# MCU.net
KiCad netlist of a schematic drawn in Altium Designer
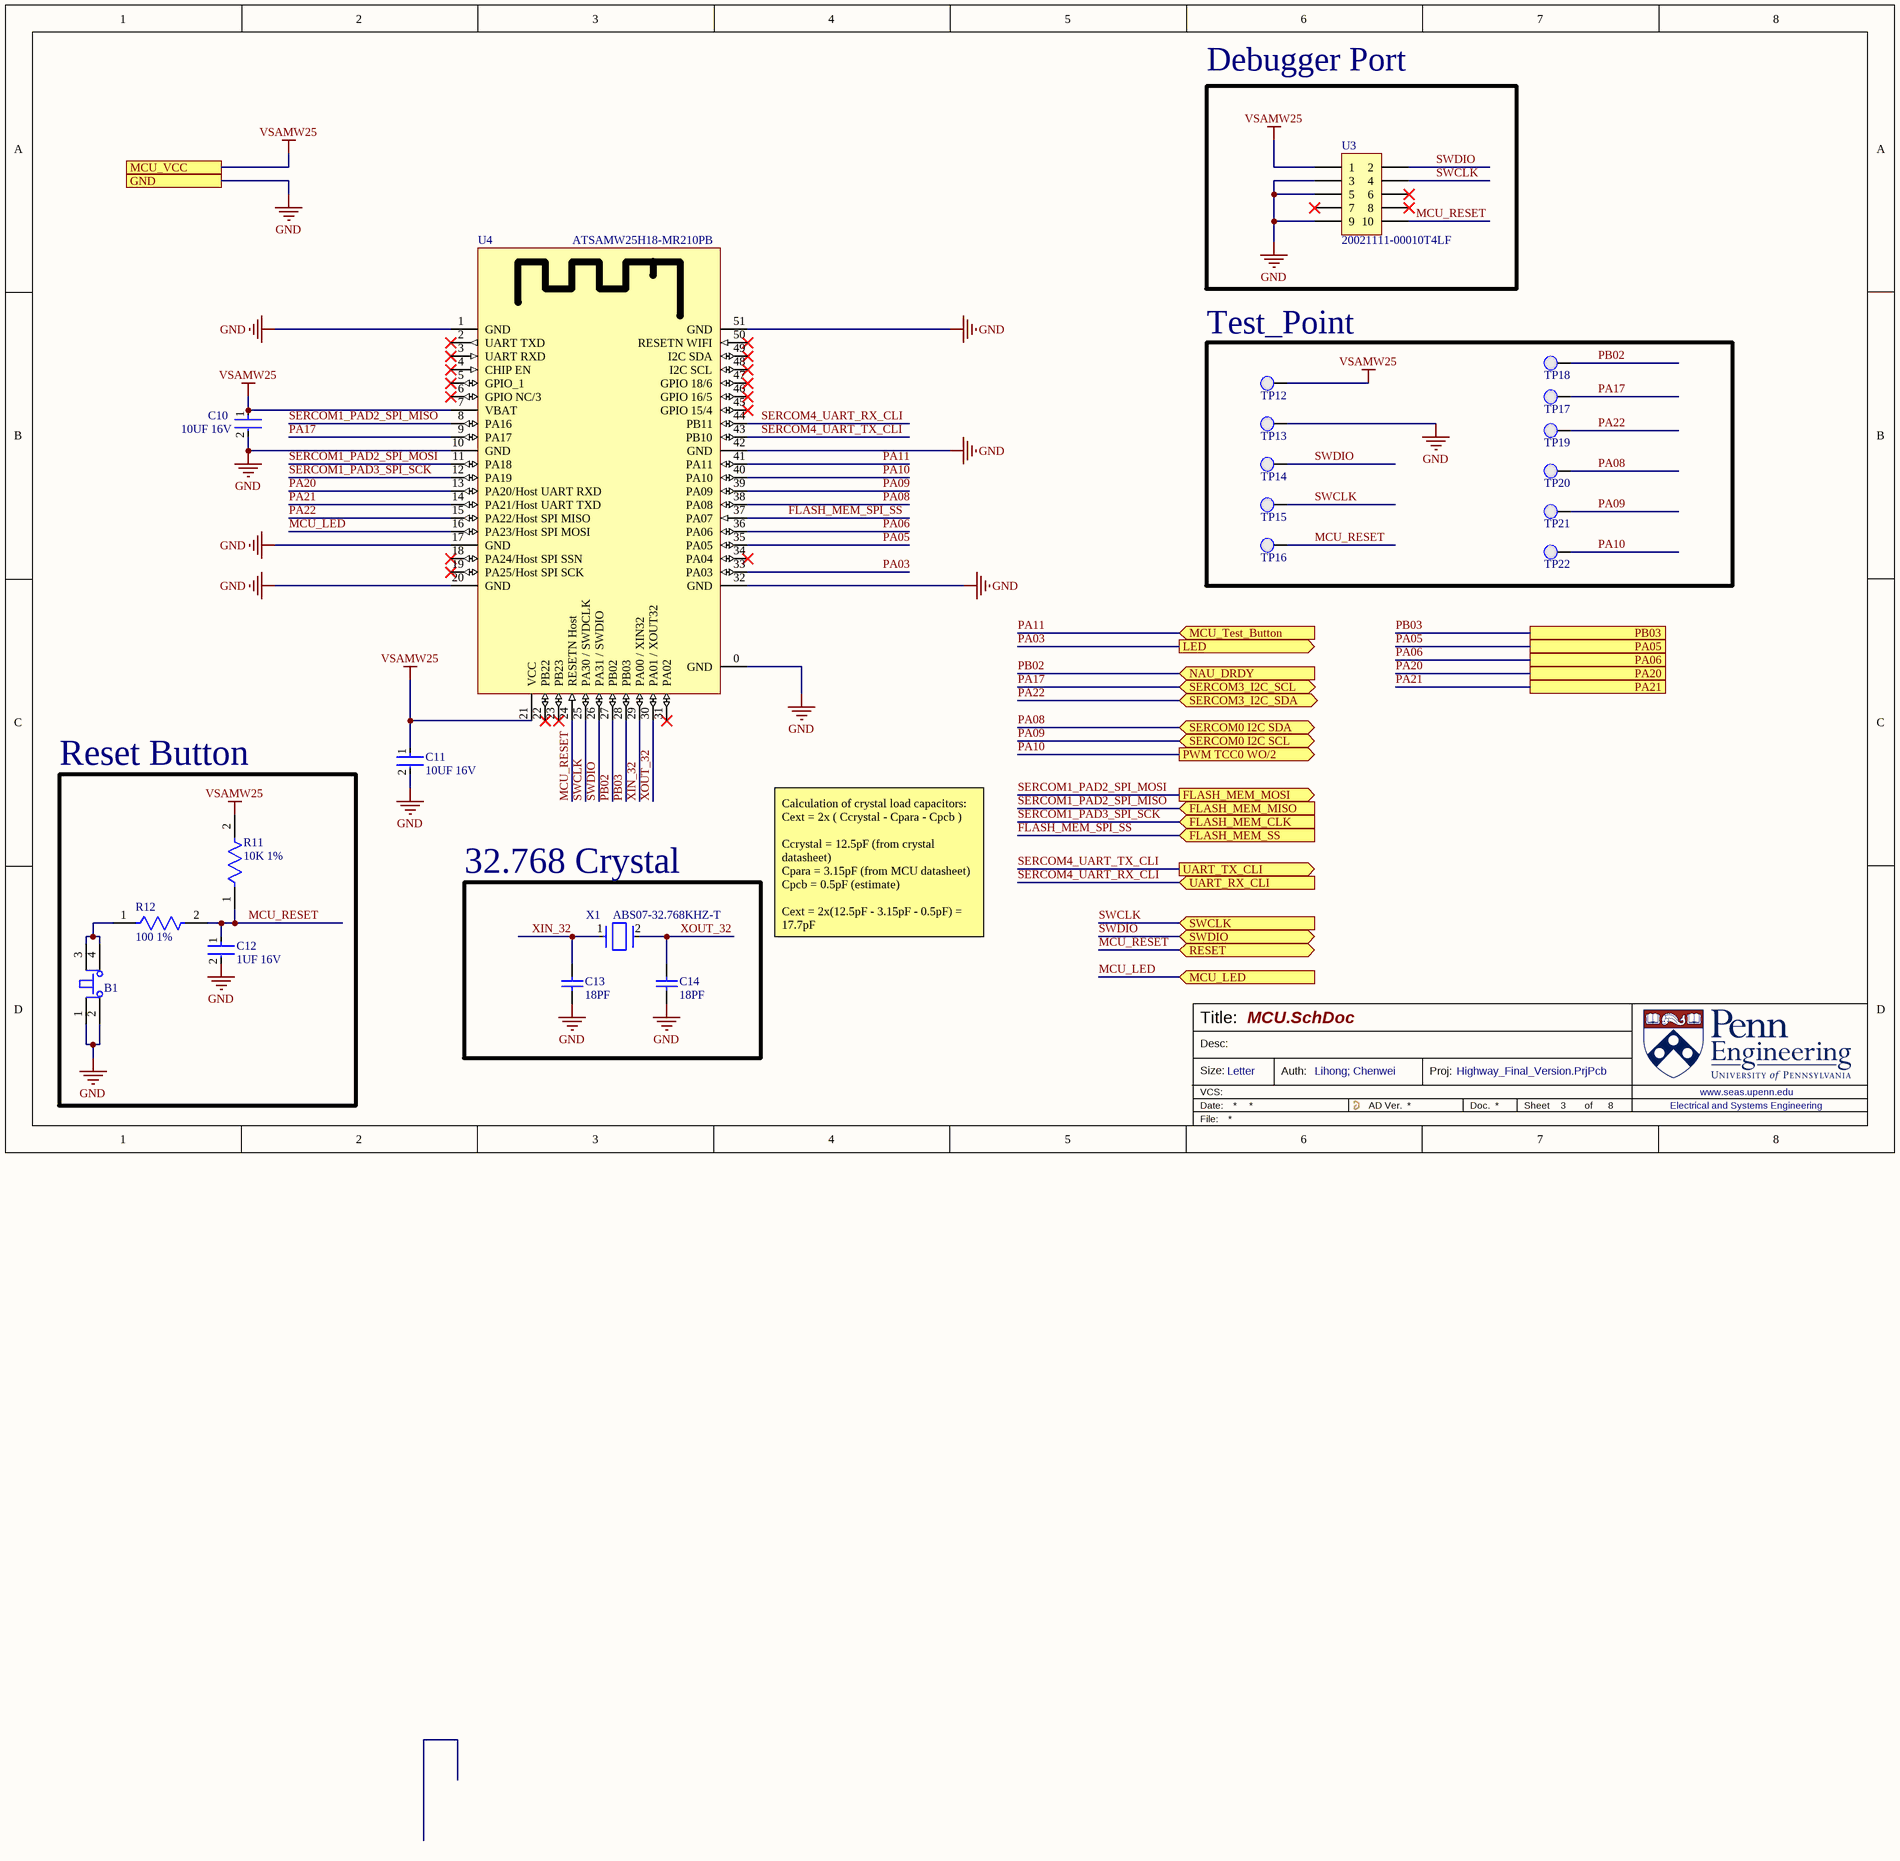
[diagram p0: MCU.SchDoc]

(export (version "E")
  (design (tool "Eeschema 10.0.6"))
  (components
    (comp (ref "B1")
      (value "PTS810SJK250SMTRLFS")
      (footprint "PTS810SJK250SMTRLFS-Footprint-1")
      (libsource (lib "University of Pennsylvania (ESE Labs)") (part "Tactile Switch 4 Pin"))
    )
    (comp (ref "C10")
      (value "10UF 16V")
      (footprint "FP-CC0603-DB-MFG")
      (description "CAP CER 10UF 6.3V X5R 0603")
      (fields (field (name "TOLERANCE") "20%"))
      (libsource (lib "Altium Content Vault") (part "e9c51b7dd13d4faca003ae77663ab08"))
    )
    (comp (ref "C11")
      (value "10UF 16V")
      (footprint "FP-CC0603-DB-MFG")
      (description "CAP CER 10UF 6.3V X5R 0603")
      (fields (field (name "TOLERANCE") "20%"))
      (libsource (lib "Altium Content Vault") (part "e9c51b7dd13d4faca003ae77663ab08"))
    )
    (comp (ref "C12")
      (value "1UF 16V")
      (footprint "FP-CC0603-DA-MFG")
      (description "CC0603 1 uF X7R 10.00% 16 V")
      (fields (field (name "MANUFACTURER") "YAGEO") (field (name "TOLERANCE") "0.1"))
      (libsource (lib "Altium Content Vault") (part "11868f565c42a9108669ba33697ecf6"))
    )
    (comp (ref "C13")
      (value "18PF")
      (footprint "CAPC1608X90X40LL10T20")
      (description "Chip Capacitor, 18 pF, +/- 5%, 50 V, -55 to 125 degC, 0603 (1608 Metric), RoHS, Tape and Reel")
      (fields (field (name "TOLERANCE") "1%"))
      (libsource (lib "Altium Content Vault") (part "CAP-NP-2"))
    )
    (comp (ref "C14")
      (value "18PF")
      (footprint "CAPC1608X90X40LL10T20")
      (description "Chip Capacitor, 18 pF, +/- 5%, 50 V, -55 to 125 degC, 0603 (1608 Metric), RoHS, Tape and Reel")
      (fields (field (name "TOLERANCE") "1%"))
      (libsource (lib "Altium Content Vault") (part "CAP-NP-2"))
    )
    (comp (ref "R11")
      (value "10K 1%")
      (footprint "FP-RNCP0603-IPC_A")
      (description "10kΩ ±1% 0.125W 0603 High Power Anti-Sulfur Thin Film Chip Resistor")
      (fields (field (name "TOLERANCE") "1%"))
      (libsource (lib "Altium Content Vault") (part "1029c3af85768c4190bb7ad29bc67b5"))
    )
    (comp (ref "R12")
      (value "100 1%")
      (footprint "FP-RMCF0603-IPC_C")
      (description "100Ω ±1% 0.1W 0603 Thick Film Chip Resistor AEC-Q200 compliant")
      (fields (field (name "TOLERANCE") "1%"))
      (libsource (lib "Altium Content Vault") (part "1029c3af85768c4190bb7ad29bc67b5"))
    )
    (comp (ref "TP12")
      (value "Test Point 0.1\"")
      (footprint "Test Point 0.1\"-Footprint-1")
      (libsource (lib "University of Pennsylvania (ESE Labs)") (part "Test Point 0.1{dblquote}-Symbol-1"))
    )
    (comp (ref "TP13")
      (value "Test Point 0.1\"")
      (footprint "Test Point 0.1\"-Footprint-1")
      (libsource (lib "University of Pennsylvania (ESE Labs)") (part "Test Point 0.1{dblquote}-Symbol-1"))
    )
    (comp (ref "TP14")
      (value "Test Point 0.1\"")
      (footprint "Test Point 0.1\"-Footprint-1")
      (libsource (lib "University of Pennsylvania (ESE Labs)") (part "Test Point 0.1{dblquote}-Symbol-1"))
    )
    (comp (ref "TP15")
      (value "Test Point 0.1\"")
      (footprint "Test Point 0.1\"-Footprint-1")
      (libsource (lib "University of Pennsylvania (ESE Labs)") (part "Test Point 0.1{dblquote}-Symbol-1"))
    )
    (comp (ref "TP16")
      (value "Test Point 0.1\"")
      (footprint "Test Point 0.1\"-Footprint-1")
      (libsource (lib "University of Pennsylvania (ESE Labs)") (part "Test Point 0.1{dblquote}-Symbol-1"))
    )
    (comp (ref "TP17")
      (value "Test Point 0.1\"")
      (footprint "Test Point 0.1\"-Footprint-1")
      (libsource (lib "University of Pennsylvania (ESE Labs)") (part "Test Point 0.1{dblquote}-Symbol-1"))
    )
    (comp (ref "TP18")
      (value "Test Point 0.1\"")
      (footprint "Test Point 0.1\"-Footprint-1")
      (libsource (lib "University of Pennsylvania (ESE Labs)") (part "Test Point 0.1{dblquote}-Symbol-1"))
    )
    (comp (ref "TP19")
      (value "Test Point 0.1\"")
      (footprint "Test Point 0.1\"-Footprint-1")
      (libsource (lib "University of Pennsylvania (ESE Labs)") (part "Test Point 0.1{dblquote}-Symbol-1"))
    )
    (comp (ref "TP20")
      (value "Test Point 0.1\"")
      (footprint "Test Point 0.1\"-Footprint-1")
      (libsource (lib "University of Pennsylvania (ESE Labs)") (part "Test Point 0.1{dblquote}-Symbol-1"))
    )
    (comp (ref "TP21")
      (value "Test Point 0.1\"")
      (footprint "Test Point 0.1\"-Footprint-1")
      (libsource (lib "University of Pennsylvania (ESE Labs)") (part "Test Point 0.1{dblquote}-Symbol-1"))
    )
    (comp (ref "TP22")
      (value "Test Point 0.1\"")
      (footprint "Test Point 0.1\"-Footprint-1")
      (libsource (lib "University of Pennsylvania (ESE Labs)") (part "Test Point 0.1{dblquote}-Symbol-1"))
    )
    (comp (ref "U3")
      (value "20021111-00010T4LF")
      (footprint "20021111-00010T4LF-Footprint-1")
      (libsource (lib "University of Pennsylvania (ESE Labs)") (part "20021111-00010T4LF-Symbol-1"))
    )
    (comp (ref "U4")
      (value "ATSAMW25H18-MR210PB")
      (footprint "SAMW25H18-MR510PB-Footprint-1")
      (description "2.7 - 4.2 V 65 Mbps 17 dbm 256 kB Flash 32 kB SRAM 802.11 b/g/n Smart Module")
      (libsource (lib "University of Pennsylvania (ESE Labs)") (part "SAMW25H18-MR510PB-Symbol-1"))
    )
    (comp (ref "X1")
      (value "ABS07-32.768KHZ-T")
      (footprint "FP-ABS07-MFG")
      (description "Crystal 32.768kHz ±20ppm (Tol) 12.5pF FUND 70kΩ 2-Pin CSMD T/R")
      (fields (field (name "TOLERANCE") "20ppm"))
      (libsource (lib "Altium Content Vault") (part "c23a69dc6c9e2f18f2079038eb95dd1"))
    )
  )
  (nets
    (net (code "1") (name "/FLASH_MEM_SPI_SS") (class "Default")
      (node (ref "U4") (pin "37") (pinfunction "PA07_37") (pintype "input"))
    )
    (net (code "2") (name "/MCU_LED") (class "Default")
      (node (ref "U4") (pin "16") (pinfunction "PA23/Host_SPI_MOSI_16") (pintype "bidirectional"))
    )
    (net (code "3") (name "/MCU_RESET") (class "Default")
      (node (ref "C12") (pin "1") (pinfunction "1_1") (pintype "passive"))
      (node (ref "R11") (pin "1") (pinfunction "1_1") (pintype "passive"))
      (node (ref "R12") (pin "2") (pinfunction "2_2") (pintype "passive"))
      (node (ref "TP16") (pin "1") (pinfunction "PAD_1") (pintype "passive"))
      (node (ref "U3") (pin "10") (pinfunction "10_10") (pintype "passive"))
      (node (ref "U4") (pin "24") (pinfunction "RESETN_Host_24") (pintype "input"))
    )
    (net (code "4") (name "/PA03") (class "Default")
      (node (ref "U4") (pin "33") (pinfunction "PA03_33") (pintype "bidirectional"))
    )
    (net (code "5") (name "/PA05") (class "Default")
      (node (ref "U4") (pin "35") (pinfunction "PA05_35") (pintype "bidirectional"))
    )
    (net (code "6") (name "/PA06") (class "Default")
      (node (ref "U4") (pin "36") (pinfunction "PA06_36") (pintype "bidirectional"))
    )
    (net (code "7") (name "/PA08") (class "Default")
      (node (ref "TP20") (pin "1") (pinfunction "PAD_1") (pintype "passive"))
      (node (ref "U4") (pin "38") (pinfunction "PA08_38") (pintype "bidirectional"))
    )
    (net (code "8") (name "/PA09") (class "Default")
      (node (ref "TP21") (pin "1") (pinfunction "PAD_1") (pintype "passive"))
      (node (ref "U4") (pin "39") (pinfunction "PA09_39") (pintype "bidirectional"))
    )
    (net (code "9") (name "/PA10") (class "Default")
      (node (ref "TP22") (pin "1") (pinfunction "PAD_1") (pintype "passive"))
      (node (ref "U4") (pin "40") (pinfunction "PA10_40") (pintype "bidirectional"))
    )
    (net (code "10") (name "/PA11") (class "Default")
      (node (ref "U4") (pin "41") (pinfunction "PA11_41") (pintype "bidirectional"))
    )
    (net (code "11") (name "/PA17") (class "Default")
      (node (ref "TP17") (pin "1") (pinfunction "PAD_1") (pintype "passive"))
      (node (ref "U4") (pin "9") (pinfunction "PA17_9") (pintype "bidirectional"))
    )
    (net (code "12") (name "/PA20") (class "Default")
      (node (ref "U4") (pin "13") (pinfunction "PA20/Host_UART_RXD_13") (pintype "bidirectional"))
    )
    (net (code "13") (name "/PA21") (class "Default")
      (node (ref "U4") (pin "14") (pinfunction "PA21/Host_UART_TXD_14") (pintype "bidirectional"))
    )
    (net (code "14") (name "/PA22") (class "Default")
      (node (ref "TP19") (pin "1") (pinfunction "PAD_1") (pintype "passive"))
      (node (ref "U4") (pin "15") (pinfunction "PA22/Host_SPI_MISO_15") (pintype "bidirectional"))
    )
    (net (code "15") (name "/PB02") (class "Default")
      (node (ref "TP18") (pin "1") (pinfunction "PAD_1") (pintype "passive"))
      (node (ref "U4") (pin "27") (pinfunction "PB02_27") (pintype "bidirectional"))
    )
    (net (code "16") (name "/PB03") (class "Default")
      (node (ref "U4") (pin "28") (pinfunction "PB03_28") (pintype "bidirectional"))
    )
    (net (code "17") (name "/SERCOM1_PAD2_SPI_MISO") (class "Default")
      (node (ref "U4") (pin "8") (pinfunction "PA16_8") (pintype "bidirectional"))
    )
    (net (code "18") (name "/SERCOM1_PAD2_SPI_MOSI") (class "Default")
      (node (ref "U4") (pin "11") (pinfunction "PA18_11") (pintype "bidirectional"))
    )
    (net (code "19") (name "/SERCOM1_PAD3_SPI_SCK") (class "Default")
      (node (ref "U4") (pin "12") (pinfunction "PA19_12") (pintype "bidirectional"))
    )
    (net (code "20") (name "/SERCOM4_UART_RX_CLI") (class "Default")
      (node (ref "U4") (pin "44") (pinfunction "PB11_44") (pintype "bidirectional"))
    )
    (net (code "21") (name "/SERCOM4_UART_TX_CLI") (class "Default")
      (node (ref "U4") (pin "43") (pinfunction "PB10_43") (pintype "bidirectional"))
    )
    (net (code "22") (name "/SWCLK") (class "Default")
      (node (ref "TP15") (pin "1") (pinfunction "PAD_1") (pintype "passive"))
      (node (ref "U3") (pin "4") (pinfunction "4_4") (pintype "passive"))
      (node (ref "U4") (pin "25") (pinfunction "PA30_/_SWDCLK_25") (pintype "bidirectional"))
    )
    (net (code "23") (name "/SWDIO") (class "Default")
      (node (ref "TP14") (pin "1") (pinfunction "PAD_1") (pintype "passive"))
      (node (ref "U3") (pin "2") (pinfunction "2_2") (pintype "passive"))
      (node (ref "U4") (pin "26") (pinfunction "PA31_/_SWDIO_26") (pintype "bidirectional"))
    )
    (net (code "24") (name "/XIN_32") (class "Default")
      (node (ref "C13") (pin "2") (pinfunction "2_2") (pintype "passive"))
      (node (ref "U4") (pin "29") (pinfunction "PA00_/_XIN32_29") (pintype "bidirectional"))
      (node (ref "X1") (pin "1") (pinfunction "1_1") (pintype "passive"))
    )
    (net (code "25") (name "/XOUT_32") (class "Default")
      (node (ref "C14") (pin "1") (pinfunction "1_1") (pintype "passive"))
      (node (ref "U4") (pin "30") (pinfunction "PA01_/_XOUT32_30") (pintype "bidirectional"))
      (node (ref "X1") (pin "2") (pinfunction "2_2") (pintype "passive"))
    )
    (net (code "26") (name "GND") (class "Default")
      (node (ref "B1") (pin "1") (pinfunction "1_1") (pintype "passive"))
      (node (ref "B1") (pin "2") (pinfunction "2_2") (pintype "passive"))
      (node (ref "C10") (pin "2") (pinfunction "2_2") (pintype "passive"))
      (node (ref "C11") (pin "2") (pinfunction "2_2") (pintype "passive"))
      (node (ref "C12") (pin "2") (pinfunction "2_2") (pintype "passive"))
      (node (ref "C13") (pin "1") (pinfunction "1_1") (pintype "passive"))
      (node (ref "C14") (pin "2") (pinfunction "2_2") (pintype "passive"))
      (node (ref "TP13") (pin "1") (pinfunction "PAD_1") (pintype "passive"))
      (node (ref "U3") (pin "3") (pinfunction "3_3") (pintype "passive"))
      (node (ref "U3") (pin "5") (pinfunction "5_5") (pintype "passive"))
      (node (ref "U3") (pin "9") (pinfunction "9_9") (pintype "passive"))
      (node (ref "U4") (pin "0") (pinfunction "GND_0") (pintype "power_in"))
      (node (ref "U4") (pin "1") (pinfunction "GND_1") (pintype "power_in"))
      (node (ref "U4") (pin "10") (pinfunction "GND_10") (pintype "power_in"))
      (node (ref "U4") (pin "17") (pinfunction "GND_17") (pintype "power_in"))
      (node (ref "U4") (pin "20") (pinfunction "GND_20") (pintype "power_in"))
      (node (ref "U4") (pin "32") (pinfunction "GND_32") (pintype "power_in"))
      (node (ref "U4") (pin "42") (pinfunction "GND_42") (pintype "power_in"))
      (node (ref "U4") (pin "51") (pinfunction "GND_51") (pintype "power_in"))
    )
    (net (code "27") (name "Net-(B1-2-Pad3)") (class "Default")
      (node (ref "B1") (pin "3") (pinfunction "2_3") (pintype "passive"))
      (node (ref "B1") (pin "4") (pinfunction "4_4") (pintype "passive"))
      (node (ref "R12") (pin "1") (pinfunction "1_1") (pintype "passive"))
    )
    (net (code "28") (name "VSAMW25") (class "Default")
      (node (ref "C10") (pin "1") (pinfunction "1_1") (pintype "passive"))
      (node (ref "C11") (pin "1") (pinfunction "1_1") (pintype "passive"))
      (node (ref "R11") (pin "2") (pinfunction "2_2") (pintype "passive"))
      (node (ref "TP12") (pin "1") (pinfunction "PAD_1") (pintype "passive"))
      (node (ref "U3") (pin "1") (pinfunction "1_1") (pintype "passive"))
      (node (ref "U4") (pin "21") (pinfunction "VCC_21") (pintype "power_in"))
      (node (ref "U4") (pin "7") (pinfunction "VBAT_7") (pintype "power_in"))
    )
    (net (code "29") (name "unconnected-(U3-Pad6)") (class "Default")
      (node (ref "U3") (pin "6") (pinfunction "6_6") (pintype "passive+no_connect"))
    )
    (net (code "30") (name "unconnected-(U3-Pad7)") (class "Default")
      (node (ref "U3") (pin "7") (pinfunction "7_7") (pintype "passive+no_connect"))
    )
    (net (code "31") (name "unconnected-(U3-Pad8)") (class "Default")
      (node (ref "U3") (pin "8") (pinfunction "8_8") (pintype "passive+no_connect"))
    )
    (net (code "32") (name "unconnected-(U4-CHIP_EN-Pad4)") (class "Default")
      (node (ref "U4") (pin "4") (pinfunction "CHIP_EN_4") (pintype "input+no_connect"))
    )
    (net (code "33") (name "unconnected-(U4-GPIO_1-Pad5)") (class "Default")
      (node (ref "U4") (pin "5") (pinfunction "GPIO_1_5") (pintype "bidirectional+no_connect"))
    )
    (net (code "34") (name "unconnected-(U4-GPIO_15{slash}4-Pad45)") (class "Default")
      (node (ref "U4") (pin "45") (pinfunction "GPIO_15/4_45") (pintype "bidirectional+no_connect"))
    )
    (net (code "35") (name "unconnected-(U4-GPIO_16{slash}5-Pad46)") (class "Default")
      (node (ref "U4") (pin "46") (pinfunction "GPIO_16/5_46") (pintype "bidirectional+no_connect"))
    )
    (net (code "36") (name "unconnected-(U4-GPIO_18{slash}6-Pad47)") (class "Default")
      (node (ref "U4") (pin "47") (pinfunction "GPIO_18/6_47") (pintype "bidirectional+no_connect"))
    )
    (net (code "37") (name "unconnected-(U4-GPIO_NC{slash}3-Pad6)") (class "Default")
      (node (ref "U4") (pin "6") (pinfunction "GPIO_NC/3_6") (pintype "bidirectional+no_connect"))
    )
    (net (code "38") (name "unconnected-(U4-I2C_SCL-Pad48)") (class "Default")
      (node (ref "U4") (pin "48") (pinfunction "I2C_SCL_48") (pintype "bidirectional+no_connect"))
    )
    (net (code "39") (name "unconnected-(U4-I2C_SDA-Pad49)") (class "Default")
      (node (ref "U4") (pin "49") (pinfunction "I2C_SDA_49") (pintype "bidirectional+no_connect"))
    )
    (net (code "40") (name "unconnected-(U4-PA02-Pad31)") (class "Default")
      (node (ref "U4") (pin "31") (pinfunction "PA02_31") (pintype "bidirectional+no_connect"))
    )
    (net (code "41") (name "unconnected-(U4-PA04-Pad34)") (class "Default")
      (node (ref "U4") (pin "34") (pinfunction "PA04_34") (pintype "bidirectional+no_connect"))
    )
    (net (code "42") (name "unconnected-(U4-PA24{slash}Host_SPI_SSN-Pad18)") (class "Default")
      (node (ref "U4") (pin "18") (pinfunction "PA24/Host_SPI_SSN_18") (pintype "bidirectional+no_connect"))
    )
    (net (code "43") (name "unconnected-(U4-PA25{slash}Host_SPI_SCK-Pad19)") (class "Default")
      (node (ref "U4") (pin "19") (pinfunction "PA25/Host_SPI_SCK_19") (pintype "bidirectional+no_connect"))
    )
    (net (code "44") (name "unconnected-(U4-PB22-Pad22)") (class "Default")
      (node (ref "U4") (pin "22") (pinfunction "PB22_22") (pintype "bidirectional+no_connect"))
    )
    (net (code "45") (name "unconnected-(U4-PB23-Pad23)") (class "Default")
      (node (ref "U4") (pin "23") (pinfunction "PB23_23") (pintype "bidirectional+no_connect"))
    )
    (net (code "46") (name "unconnected-(U4-RESETN_WIFI-Pad50)") (class "Default")
      (node (ref "U4") (pin "50") (pinfunction "RESETN_WIFI_50") (pintype "input+no_connect"))
    )
    (net (code "47") (name "unconnected-(U4-UART_RXD-Pad3)") (class "Default")
      (node (ref "U4") (pin "3") (pinfunction "UART_RXD_3") (pintype "input+no_connect"))
    )
    (net (code "48") (name "unconnected-(U4-UART_TXD-Pad2)") (class "Default")
      (node (ref "U4") (pin "2") (pinfunction "UART_TXD_2") (pintype "output+no_connect"))
    )
  )
)
